# Own_USB-C_Breakout_pro_v4_0_Final_AR.net
KiCad netlist of a schematic drawn in EAGLE
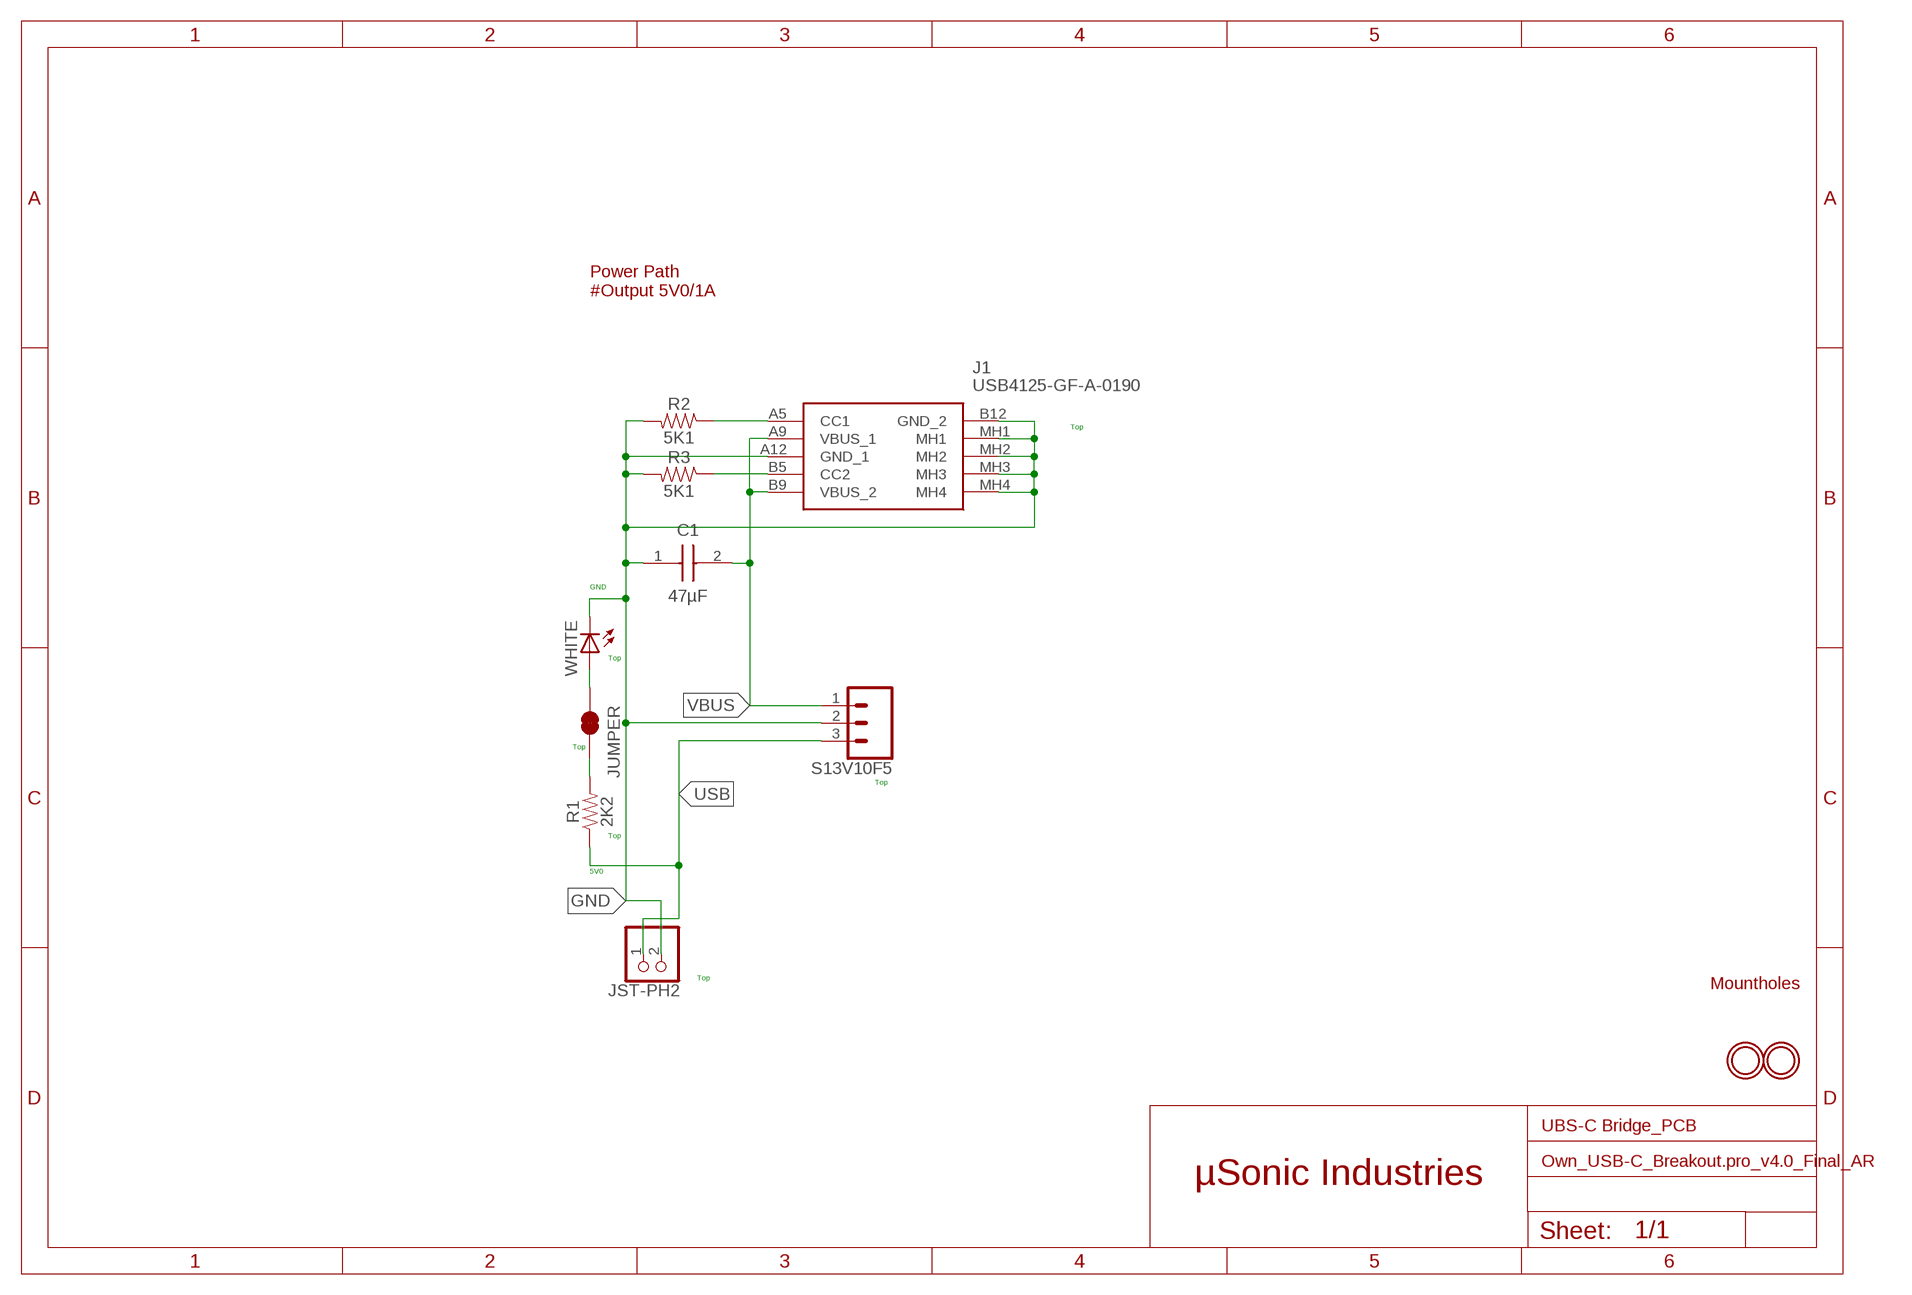
[diagram p0: schematic, sheet 1]

(export (version "E")
  (design (tool "Eeschema 10.0.6"))
  (components
    (comp (ref "C1")
      (value "47µF")
      (footprint "eagle-import:CAPC5750X310N")
      (fields
        (field (name "MANUFACTURER_PART_NUMBER") "C5750X7R1V476M230KC")
        (field (name "MOUSER_PART_NUMBER") "810-C5750X7R1V476M23")
      )
      (libsource (lib "eagle-import") (part "C5750X7R1V476M230KC"))
    )
    (comp (ref "J1")
      (value "USB4125-GF-A-0190")
      (footprint "eagle-import:USB4125GFA0190")
      (fields (field (name "MOUSER_PART_NUMBER") "640-USB4125-GF-A-190"))
      (libsource (lib "eagle-import") (part "USB4125-GF-A-0190"))
    )
    (comp (ref "JST-PH2")
      (value "JST_2PINOWN")
      (footprint "eagle-import:JST-PH-2-THMOWN")
      (libsource (lib "eagle-import") (part "JST_2PINOWN"))
    )
    (comp (ref "JUMPER")
      (value "JUMPER-SMT_2_NC_TRACE_SILK")
      (footprint "eagle-import:SMT-JUMPER_2_NC_TRACE_SILK")
      (libsource (lib "eagle-import") (part "JUMPER-SMT_2_NC_TRACE_SILK"))
    )
    (comp (ref "R1")
      (value "2K2")
      (footprint "eagle-import:0805")
      (libsource (lib "eagle-import") (part "RESISTOR0805"))
    )
    (comp (ref "R2")
      (value "5K1")
      (footprint "eagle-import:0805")
      (libsource (lib "eagle-import") (part "RESISTOR0805"))
    )
    (comp (ref "R3")
      (value "5K1")
      (footprint "eagle-import:0805")
      (libsource (lib "eagle-import") (part "RESISTOR0805"))
    )
    (comp (ref "S13V10F5")
      (value "CONN_031X03_NO_SILK")
      (footprint "eagle-import:1X03_NO_SILK")
      (libsource (lib "eagle-import") (part "CONN_031X03_NO_SILK"))
    )
    (comp (ref "U$1")
      (value "MOUNTINGHOLE2.5")
      (footprint "eagle-import:MOUNTINGHOLE_2.5_PLATED")
      (libsource (lib "eagle-import") (part "MOUNTINGHOLE2.5"))
    )
    (comp (ref "U$2")
      (value "MOUNTINGHOLE2.5")
      (footprint "eagle-import:MOUNTINGHOLE_2.5_PLATED")
      (libsource (lib "eagle-import") (part "MOUNTINGHOLE2.5"))
    )
    (comp (ref "WHITE")
      (value "LEDCHIPLED_0805")
      (footprint "eagle-import:CHIPLED_0805")
      (libsource (lib "eagle-import") (part "LEDCHIPLED_0805"))
    )
  )
  (nets
    (net (code "1") (name "GND") (class "Default")
      (node (ref "C1") (pin "1") (pinfunction "1_1") (pintype "bidirectional"))
      (node (ref "J1") (pin "A12") (pinfunction "GND_1_A12") (pintype "bidirectional"))
      (node (ref "J1") (pin "B12") (pinfunction "GND_2_B12") (pintype "bidirectional"))
      (node (ref "J1") (pin "MH1") (pinfunction "MH1_MH1") (pintype "bidirectional"))
      (node (ref "J1") (pin "MH2") (pinfunction "MH2_MH2") (pintype "bidirectional"))
      (node (ref "J1") (pin "MH3") (pinfunction "MH3_MH3") (pintype "bidirectional"))
      (node (ref "J1") (pin "MH4") (pinfunction "MH4_MH4") (pintype "bidirectional"))
      (node (ref "JST-PH2") (pin "2") (pinfunction "1_2") (pintype "passive"))
      (node (ref "R2") (pin "2") (pinfunction "2_2") (pintype "passive"))
      (node (ref "R3") (pin "2") (pinfunction "2_2") (pintype "passive"))
      (node (ref "S13V10F5") (pin "2") (pinfunction "2_2") (pintype "passive"))
      (node (ref "WHITE") (pin "C") (pinfunction "C_C") (pintype "passive"))
    )
    (net (code "2") (name "Net-(J1-CC1)") (class "Default")
      (node (ref "J1") (pin "A5") (pinfunction "CC1_A5") (pintype "bidirectional"))
      (node (ref "R2") (pin "1") (pinfunction "1_1") (pintype "passive"))
    )
    (net (code "3") (name "Net-(J1-CC2)") (class "Default")
      (node (ref "J1") (pin "B5") (pinfunction "CC2_B5") (pintype "bidirectional"))
      (node (ref "R3") (pin "1") (pinfunction "1_1") (pintype "passive"))
    )
    (net (code "4") (name "Net-(JUMPER-Pad1)") (class "Default")
      (node (ref "JUMPER") (pin "1") (pinfunction "1_1") (pintype "passive"))
      (node (ref "WHITE") (pin "A") (pinfunction "A_A") (pintype "passive"))
    )
    (net (code "5") (name "Net-(JUMPER-Pad2)") (class "Default")
      (node (ref "JUMPER") (pin "2") (pinfunction "2_2") (pintype "passive"))
      (node (ref "R1") (pin "2") (pinfunction "2_2") (pintype "passive"))
    )
    (net (code "6") (name "USB") (class "Default")
      (node (ref "JST-PH2") (pin "1") (pinfunction "2_1") (pintype "passive"))
      (node (ref "R1") (pin "1") (pinfunction "1_1") (pintype "passive"))
      (node (ref "S13V10F5") (pin "3") (pinfunction "3_3") (pintype "passive"))
    )
    (net (code "7") (name "VBUS") (class "Default")
      (node (ref "C1") (pin "2") (pinfunction "2_2") (pintype "bidirectional"))
      (node (ref "J1") (pin "A9") (pinfunction "VBUS_1_A9") (pintype "bidirectional"))
      (node (ref "J1") (pin "B9") (pinfunction "VBUS_2_B9") (pintype "bidirectional"))
      (node (ref "S13V10F5") (pin "1") (pinfunction "1_1") (pintype "passive"))
    )
  )
)
